# USB_HS_DEVICE.net
KiCad netlist of a schematic drawn in Altium Designer
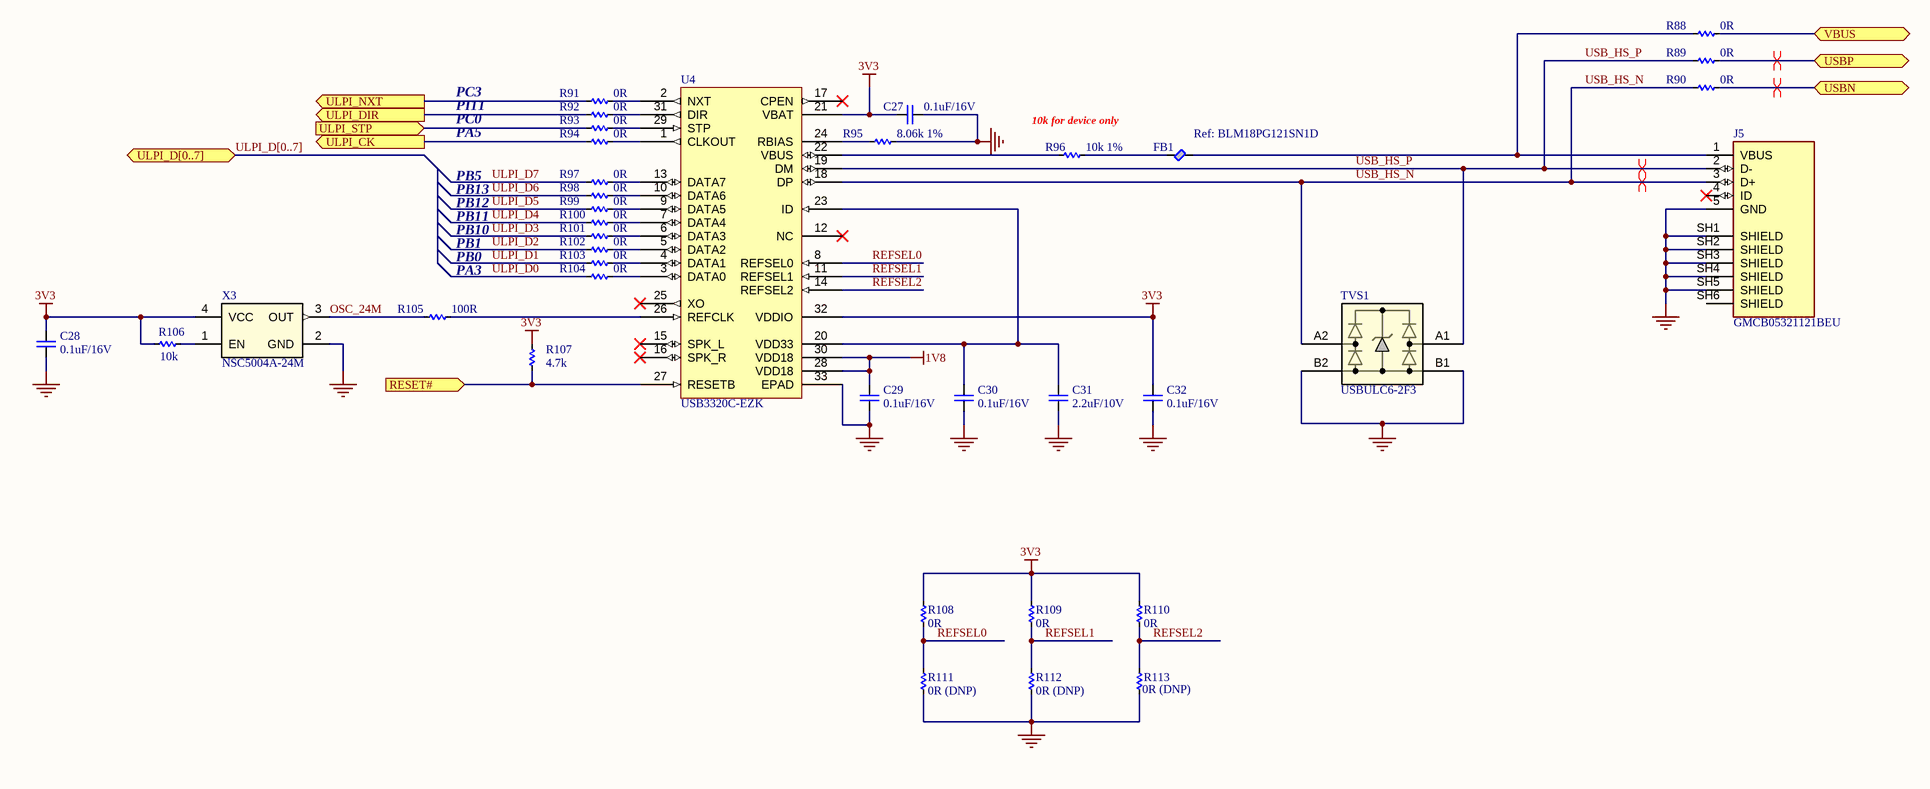
[diagram p0: USB_HS_DEVICE.SchDoc]

(export (version "E")
  (design (tool "Eeschema 10.0.6"))
  (components
    (comp (ref "C27")
      (value "0.1uF/16V")
      (footprint "CAP_C_1608X80")
      (description "CAP_Chip")
      (libsource (lib "LABLIB") (part "CAP_SMD"))
    )
    (comp (ref "C28")
      (value "0.1uF/16V")
      (footprint "CAP_C_1608X80")
      (description "CAP_Chip")
      (libsource (lib "LABLIB") (part "CAP_SMD"))
    )
    (comp (ref "C29")
      (value "0.1uF/16V")
      (footprint "CAP_C_1608X80")
      (description "CAP_Chip")
      (libsource (lib "LABLIB") (part "CAP_SMD"))
    )
    (comp (ref "C30")
      (value "0.1uF/16V")
      (footprint "CAP_C_1608X80")
      (description "CAP_Chip")
      (libsource (lib "LABLIB") (part "CAP_SMD"))
    )
    (comp (ref "C31")
      (value "2.2uF/10V")
      (footprint "CAP_C_1608X80")
      (description "CAP_Chip")
      (libsource (lib "LABLIB") (part "CAP_SMD"))
    )
    (comp (ref "C32")
      (value "0.1uF/16V")
      (footprint "CAP_C_1608X80")
      (description "CAP_Chip")
      (libsource (lib "LABLIB") (part "CAP_SMD"))
    )
    (comp (ref "FB1")
      (value "FB")
      (footprint "IND_1608x65")
      (description "FERRITE BEAD")
      (libsource (lib "COMM_SCHLIB") (part "FB"))
    )
    (comp (ref "J5")
      (value "GMCB05321121BEU")
      (footprint "AMPHENOL_GMCB05321121BEU")
      (description "Micro USB 2.0 Type B Receptacle Right Angle SMT, Tape and Reel Packaging")
      (fields (field (name "MF") "Amphenol Commercial Products"))
      (libsource (lib "COMM_SCHLIB") (part "GMCB05321121BEU"))
    )
    (comp (ref "R88")
      (value "0R")
      (footprint "RES_C_1608X60")
      (description "RES")
      (libsource (lib "LABLIB") (part "_RES_B_2"))
    )
    (comp (ref "R89")
      (value "0R")
      (footprint "RES_C_1608X60")
      (description "RES")
      (libsource (lib "LABLIB") (part "_RES_B_2"))
    )
    (comp (ref "R90")
      (value "0R")
      (footprint "RES_C_1608X60")
      (description "RES")
      (libsource (lib "LABLIB") (part "_RES_B_2"))
    )
    (comp (ref "R91")
      (value "0R")
      (footprint "RES_C_1608X60")
      (description "RES")
      (libsource (lib "LABLIB") (part "_RES_B_2"))
    )
    (comp (ref "R92")
      (value "0R")
      (footprint "RES_C_1608X60")
      (description "RES")
      (libsource (lib "LABLIB") (part "_RES_B_2"))
    )
    (comp (ref "R93")
      (value "0R")
      (footprint "RES_C_1608X60")
      (description "RES")
      (libsource (lib "LABLIB") (part "_RES_B_2"))
    )
    (comp (ref "R94")
      (value "0R")
      (footprint "RES_C_1608X60")
      (description "RES")
      (libsource (lib "LABLIB") (part "_RES_B_2"))
    )
    (comp (ref "R95")
      (value "8.06k 1%")
      (footprint "RES_C_1608X60")
      (description "RES")
      (libsource (lib "LABLIB") (part "_RES_B_2"))
    )
    (comp (ref "R96")
      (value "10k 1%")
      (footprint "RES_C_1608X60")
      (description "RES")
      (libsource (lib "LABLIB") (part "_RES_B_2"))
    )
    (comp (ref "R97")
      (value "0R")
      (footprint "RES_C_1608X60")
      (description "RES")
      (libsource (lib "LABLIB") (part "_RES_B_2"))
    )
    (comp (ref "R98")
      (value "0R")
      (footprint "RES_C_1608X60")
      (description "RES")
      (libsource (lib "LABLIB") (part "_RES_B_2"))
    )
    (comp (ref "R99")
      (value "0R")
      (footprint "RES_C_1608X60")
      (description "RES")
      (libsource (lib "LABLIB") (part "_RES_B_2"))
    )
    (comp (ref "R100")
      (value "0R")
      (footprint "RES_C_1608X60")
      (description "RES")
      (libsource (lib "LABLIB") (part "_RES_B_2"))
    )
    (comp (ref "R101")
      (value "0R")
      (footprint "RES_C_1608X60")
      (description "RES")
      (libsource (lib "LABLIB") (part "_RES_B_2"))
    )
    (comp (ref "R102")
      (value "0R")
      (footprint "RES_C_1608X60")
      (description "RES")
      (libsource (lib "LABLIB") (part "_RES_B_2"))
    )
    (comp (ref "R103")
      (value "0R")
      (footprint "RES_C_1608X60")
      (description "RES")
      (libsource (lib "LABLIB") (part "_RES_B_2"))
    )
    (comp (ref "R104")
      (value "0R")
      (footprint "RES_C_1608X60")
      (description "RES")
      (libsource (lib "LABLIB") (part "_RES_B_2"))
    )
    (comp (ref "R105")
      (value "100R")
      (footprint "RES_C_1608X60")
      (description "RES")
      (libsource (lib "LABLIB") (part "_RES_B_2"))
    )
    (comp (ref "R106")
      (value "10k")
      (footprint "RES_C_1608X60")
      (description "RES")
      (libsource (lib "LABLIB") (part "_RES_B_2"))
    )
    (comp (ref "R107")
      (value "4.7k")
      (footprint "RES_C_1608X60")
      (description "RES")
      (libsource (lib "LABLIB") (part "_RES_B_2"))
    )
    (comp (ref "R108")
      (value "0R")
      (footprint "RES_C_1608X60")
      (description "RES")
      (libsource (lib "LABLIB") (part "_RES_B_2"))
    )
    (comp (ref "R109")
      (value "0R")
      (footprint "RES_C_1608X60")
      (description "RES")
      (libsource (lib "LABLIB") (part "_RES_B_2"))
    )
    (comp (ref "R110")
      (value "0R")
      (footprint "RES_C_1608X60")
      (description "RES")
      (libsource (lib "LABLIB") (part "_RES_B_2"))
    )
    (comp (ref "R111")
      (value "0R (DNP)")
      (footprint "RES_C_1608X60")
      (description "RES")
      (libsource (lib "LABLIB") (part "_RES_B_2"))
    )
    (comp (ref "R112")
      (value "0R (DNP)")
      (footprint "RES_C_1608X60")
      (description "RES")
      (libsource (lib "LABLIB") (part "_RES_B_2"))
    )
    (comp (ref "R113")
      (value "0R (DNP)")
      (footprint "RES_C_1608X60")
      (description "RES")
      (libsource (lib "LABLIB") (part "_RES_B_2"))
    )
    (comp (ref "TVS1")
      (value "USBULC6-2F3")
      (footprint "FLIPCHIP4_USBUL_STM")
      (description "TVS DIODE 3VWM 4FLIPCHIP")
      (fields (field (name "COPYRIGHT") "Copyright (C) 2025 Ultra Librarian. All rights reserved."))
      (libsource (lib "COMM_SCHLIB") (part "USBULC6-2F3"))
    )
    (comp (ref "U4")
      (value "USB3320C-EZK")
      (footprint "QFN32_5X5MC_MCH")
      (description "IC TRANSCEIVER HALF 1/1 32QFN")
      (libsource (lib "COMM_SCHLIB") (part "USB3320C-EZK"))
    )
    (comp (ref "X3")
      (value "NSC5004A-24M")
      (footprint "NSC5004D-25M")
      (description "XTAL OSC XO 24.0000MHZ CMOS SMD")
      (fields
        (field (name "MANUFACTURER_PART_NUMBER") "NSC5004A-25M")
        (field (name "COPYRIGHT") "Copyright (C) 2025 Ultra Librarian. All rights reserved.")
      )
      (libsource (lib "COMM_SCHLIB") (part "NSC5004D-25M"))
    )
  )
  (nets
    (net (code "1") (name "/OSC_24M") (class "Default")
      (node (ref "R105") (pin "2") (pinfunction "2_2") (pintype "passive"))
      (node (ref "X3") (pin "3") (pinfunction "OUT_3") (pintype "output"))
    )
    (net (code "2") (name "/REFSEL0") (class "Default")
      (node (ref "R108") (pin "2") (pinfunction "2_2") (pintype "passive"))
      (node (ref "R111") (pin "1") (pinfunction "1_1") (pintype "passive"))
      (node (ref "U4") (pin "8") (pinfunction "REFSEL0_8") (pintype "input"))
    )
    (net (code "3") (name "/REFSEL1") (class "Default")
      (node (ref "R109") (pin "2") (pinfunction "2_2") (pintype "passive"))
      (node (ref "R112") (pin "1") (pinfunction "1_1") (pintype "passive"))
      (node (ref "U4") (pin "11") (pinfunction "REFSEL1_11") (pintype "input"))
    )
    (net (code "4") (name "/REFSEL2") (class "Default")
      (node (ref "R110") (pin "2") (pinfunction "2_2") (pintype "passive"))
      (node (ref "R113") (pin "1") (pinfunction "1_1") (pintype "passive"))
      (node (ref "U4") (pin "14") (pinfunction "REFSEL2_14") (pintype "input"))
    )
    (net (code "5") (name "/RESET#") (class "Default")
      (node (ref "R107") (pin "2") (pinfunction "2_2") (pintype "passive"))
      (node (ref "U4") (pin "27") (pinfunction "RESETB_27") (pintype "input"))
    )
    (net (code "6") (name "/ULPI_CK") (class "Default")
      (node (ref "R94") (pin "2") (pinfunction "2_2") (pintype "passive"))
    )
    (net (code "7") (name "/ULPI_D0") (class "Default")
      (node (ref "R104") (pin "2") (pinfunction "2_2") (pintype "passive"))
    )
    (net (code "8") (name "/ULPI_D1") (class "Default")
      (node (ref "R103") (pin "2") (pinfunction "2_2") (pintype "passive"))
    )
    (net (code "9") (name "/ULPI_D2") (class "Default")
      (node (ref "R102") (pin "2") (pinfunction "2_2") (pintype "passive"))
    )
    (net (code "10") (name "/ULPI_D3") (class "Default")
      (node (ref "R101") (pin "2") (pinfunction "2_2") (pintype "passive"))
    )
    (net (code "11") (name "/ULPI_D4") (class "Default")
      (node (ref "R100") (pin "2") (pinfunction "2_2") (pintype "passive"))
    )
    (net (code "12") (name "/ULPI_D5") (class "Default")
      (node (ref "R99") (pin "2") (pinfunction "2_2") (pintype "passive"))
    )
    (net (code "13") (name "/ULPI_D6") (class "Default")
      (node (ref "R98") (pin "2") (pinfunction "2_2") (pintype "passive"))
    )
    (net (code "14") (name "/ULPI_D7") (class "Default")
      (node (ref "R97") (pin "2") (pinfunction "2_2") (pintype "passive"))
    )
    (net (code "15") (name "/ULPI_DIR") (class "Default")
      (node (ref "R92") (pin "2") (pinfunction "2_2") (pintype "passive"))
    )
    (net (code "17") (name "/ULPI_NXT") (class "Default")
      (node (ref "R91") (pin "2") (pinfunction "2_2") (pintype "passive"))
    )
    (net (code "18") (name "/ULPI_STP") (class "Default")
      (node (ref "R93") (pin "2") (pinfunction "2_2") (pintype "passive"))
    )
    (net (code "19") (name "/USBN") (class "Default")
      (node (ref "R90") (pin "2") (pinfunction "2_2") (pintype "passive"))
    )
    (net (code "20") (name "/USBP") (class "Default")
      (node (ref "R89") (pin "2") (pinfunction "2_2") (pintype "passive"))
    )
    (net (code "21") (name "/USB_HS_N") (class "Default")
      (node (ref "J5") (pin "3") (pinfunction "D+_3") (pintype "bidirectional"))
      (node (ref "R90") (pin "1") (pinfunction "1_1") (pintype "passive"))
      (node (ref "TVS1") (pin "A2") (pinfunction "A2_A2") (pintype "passive"))
      (node (ref "U4") (pin "18") (pinfunction "DP_18") (pintype "bidirectional"))
    )
    (net (code "22") (name "/USB_HS_P") (class "Default")
      (node (ref "J5") (pin "2") (pinfunction "D-_2") (pintype "bidirectional"))
      (node (ref "R89") (pin "1") (pinfunction "1_1") (pintype "passive"))
      (node (ref "TVS1") (pin "A1") (pinfunction "A1_A1") (pintype "passive"))
      (node (ref "U4") (pin "19") (pinfunction "DM_19") (pintype "bidirectional"))
    )
    (net (code "23") (name "/VBUS") (class "Default")
      (node (ref "R88") (pin "2") (pinfunction "2_2") (pintype "passive"))
    )
    (net (code "24") (name "1V8") (class "Default")
      (node (ref "C29") (pin "2") (pinfunction "2_2") (pintype "passive"))
      (node (ref "U4") (pin "28") (pinfunction "VDD18_28") (pintype "power_in"))
      (node (ref "U4") (pin "30") (pinfunction "VDD18_30") (pintype "power_in"))
    )
    (net (code "25") (name "3V3") (class "Default")
      (node (ref "C27") (pin "2") (pinfunction "2_2") (pintype "passive"))
      (node (ref "C28") (pin "2") (pinfunction "2_2") (pintype "passive"))
      (node (ref "C32") (pin "2") (pinfunction "2_2") (pintype "passive"))
      (node (ref "R106") (pin "2") (pinfunction "2_2") (pintype "passive"))
      (node (ref "R107") (pin "1") (pinfunction "1_1") (pintype "passive"))
      (node (ref "R108") (pin "1") (pinfunction "1_1") (pintype "passive"))
      (node (ref "R109") (pin "1") (pinfunction "1_1") (pintype "passive"))
      (node (ref "R110") (pin "1") (pinfunction "1_1") (pintype "passive"))
      (node (ref "U4") (pin "21") (pinfunction "VBAT_21") (pintype "power_in"))
      (node (ref "U4") (pin "32") (pinfunction "VDDIO_32") (pintype "power_in"))
      (node (ref "X3") (pin "4") (pinfunction "VCC_4") (pintype "power_in"))
    )
    (net (code "26") (name "GND") (class "Default")
      (node (ref "C27") (pin "1") (pinfunction "1_1") (pintype "passive"))
      (node (ref "C28") (pin "1") (pinfunction "1_1") (pintype "passive"))
      (node (ref "C29") (pin "1") (pinfunction "1_1") (pintype "passive"))
      (node (ref "C30") (pin "1") (pinfunction "1_1") (pintype "passive"))
      (node (ref "C31") (pin "1") (pinfunction "1_1") (pintype "passive"))
      (node (ref "C32") (pin "1") (pinfunction "1_1") (pintype "passive"))
      (node (ref "J5") (pin "5") (pinfunction "GND_5") (pintype "power_in"))
      (node (ref "J5") (pin "SH1") (pinfunction "SHIELD_SH1") (pintype "passive"))
      (node (ref "J5") (pin "SH2") (pinfunction "SHIELD_SH2") (pintype "passive"))
      (node (ref "J5") (pin "SH3") (pinfunction "SHIELD_SH3") (pintype "passive"))
      (node (ref "J5") (pin "SH4") (pinfunction "SHIELD_SH4") (pintype "passive"))
      (node (ref "J5") (pin "SH5") (pinfunction "SHIELD_SH5") (pintype "passive"))
      (node (ref "R111") (pin "2") (pinfunction "2_2") (pintype "passive"))
      (node (ref "R112") (pin "2") (pinfunction "2_2") (pintype "passive"))
      (node (ref "R113") (pin "2") (pinfunction "2_2") (pintype "passive"))
      (node (ref "R95") (pin "2") (pinfunction "2_2") (pintype "passive"))
      (node (ref "TVS1") (pin "B1") (pinfunction "B1_B1") (pintype "passive"))
      (node (ref "TVS1") (pin "B2") (pinfunction "B2_B2") (pintype "passive"))
      (node (ref "U4") (pin "33") (pinfunction "EPAD_33") (pintype "passive"))
      (node (ref "X3") (pin "2") (pinfunction "GND_2") (pintype "power_in"))
    )
    (net (code "27") (name "Net-(FB1-Pad1)") (class "Default")
      (node (ref "FB1") (pin "1") (pinfunction "1_1") (pintype "passive"))
      (node (ref "R96") (pin "2") (pinfunction "2_2") (pintype "passive"))
    )
    (net (code "28") (name "Net-(J5-VBUS)") (class "Default")
      (node (ref "FB1") (pin "2") (pinfunction "2_2") (pintype "passive"))
      (node (ref "J5") (pin "1") (pinfunction "VBUS_1") (pintype "power_in"))
      (node (ref "R88") (pin "1") (pinfunction "1_1") (pintype "passive"))
    )
    (net (code "29") (name "Net-(U4-CLKOUT)") (class "Default")
      (node (ref "R94") (pin "1") (pinfunction "1_1") (pintype "passive"))
      (node (ref "U4") (pin "1") (pinfunction "CLKOUT_1") (pintype "output"))
    )
    (net (code "30") (name "Net-(U4-DATA0)") (class "Default")
      (node (ref "R104") (pin "1") (pinfunction "1_1") (pintype "passive"))
      (node (ref "U4") (pin "3") (pinfunction "DATA0_3") (pintype "bidirectional"))
    )
    (net (code "31") (name "Net-(U4-DATA1)") (class "Default")
      (node (ref "R103") (pin "1") (pinfunction "1_1") (pintype "passive"))
      (node (ref "U4") (pin "4") (pinfunction "DATA1_4") (pintype "bidirectional"))
    )
    (net (code "32") (name "Net-(U4-DATA2)") (class "Default")
      (node (ref "R102") (pin "1") (pinfunction "1_1") (pintype "passive"))
      (node (ref "U4") (pin "5") (pinfunction "DATA2_5") (pintype "bidirectional"))
    )
    (net (code "33") (name "Net-(U4-DATA3)") (class "Default")
      (node (ref "R101") (pin "1") (pinfunction "1_1") (pintype "passive"))
      (node (ref "U4") (pin "6") (pinfunction "DATA3_6") (pintype "bidirectional"))
    )
    (net (code "34") (name "Net-(U4-DATA4)") (class "Default")
      (node (ref "R100") (pin "1") (pinfunction "1_1") (pintype "passive"))
      (node (ref "U4") (pin "7") (pinfunction "DATA4_7") (pintype "bidirectional"))
    )
    (net (code "35") (name "Net-(U4-DATA5)") (class "Default")
      (node (ref "R99") (pin "1") (pinfunction "1_1") (pintype "passive"))
      (node (ref "U4") (pin "9") (pinfunction "DATA5_9") (pintype "bidirectional"))
    )
    (net (code "36") (name "Net-(U4-DATA6)") (class "Default")
      (node (ref "R98") (pin "1") (pinfunction "1_1") (pintype "passive"))
      (node (ref "U4") (pin "10") (pinfunction "DATA6_10") (pintype "bidirectional"))
    )
    (net (code "37") (name "Net-(U4-DATA7)") (class "Default")
      (node (ref "R97") (pin "1") (pinfunction "1_1") (pintype "passive"))
      (node (ref "U4") (pin "13") (pinfunction "DATA7_13") (pintype "bidirectional"))
    )
    (net (code "38") (name "Net-(U4-DIR)") (class "Default")
      (node (ref "R92") (pin "1") (pinfunction "1_1") (pintype "passive"))
      (node (ref "U4") (pin "31") (pinfunction "DIR_31") (pintype "output"))
    )
    (net (code "39") (name "Net-(U4-ID)") (class "Default")
      (node (ref "C30") (pin "2") (pinfunction "2_2") (pintype "passive"))
      (node (ref "C31") (pin "2") (pinfunction "2_2") (pintype "passive"))
      (node (ref "U4") (pin "20") (pinfunction "VDD33_20") (pintype "power_in"))
      (node (ref "U4") (pin "23") (pinfunction "ID_23") (pintype "input"))
    )
    (net (code "40") (name "Net-(U4-NXT)") (class "Default")
      (node (ref "R91") (pin "1") (pinfunction "1_1") (pintype "passive"))
      (node (ref "U4") (pin "2") (pinfunction "NXT_2") (pintype "output"))
    )
    (net (code "41") (name "Net-(U4-RBIAS)") (class "Default")
      (node (ref "R95") (pin "1") (pinfunction "1_1") (pintype "passive"))
      (node (ref "U4") (pin "24") (pinfunction "RBIAS_24") (pintype "passive"))
    )
    (net (code "42") (name "Net-(U4-REFCLK)") (class "Default")
      (node (ref "R105") (pin "1") (pinfunction "1_1") (pintype "passive"))
      (node (ref "U4") (pin "26") (pinfunction "REFCLK_26") (pintype "input"))
    )
    (net (code "43") (name "Net-(U4-STP)") (class "Default")
      (node (ref "R93") (pin "1") (pinfunction "1_1") (pintype "passive"))
      (node (ref "U4") (pin "29") (pinfunction "STP_29") (pintype "input"))
    )
    (net (code "44") (name "Net-(U4-VBUS)") (class "Default")
      (node (ref "R96") (pin "1") (pinfunction "1_1") (pintype "passive"))
      (node (ref "U4") (pin "22") (pinfunction "VBUS_22") (pintype "bidirectional"))
    )
    (net (code "45") (name "Net-(X3-EN)") (class "Default")
      (node (ref "R106") (pin "1") (pinfunction "1_1") (pintype "passive"))
      (node (ref "X3") (pin "1") (pinfunction "EN_1") (pintype "passive"))
    )
    (net (code "46") (name "unconnected-(J5-ID-Pad4)") (class "Default")
      (node (ref "J5") (pin "4") (pinfunction "ID_4") (pintype "bidirectional+no_connect"))
    )
    (net (code "47") (name "unconnected-(J5-SHIELD-PadSH6)") (class "Default")
      (node (ref "J5") (pin "SH6") (pinfunction "SHIELD_SH6") (pintype "passive"))
    )
    (net (code "48") (name "unconnected-(U4-CPEN-Pad17)") (class "Default")
      (node (ref "U4") (pin "17") (pinfunction "CPEN_17") (pintype "output+no_connect"))
    )
    (net (code "49") (name "unconnected-(U4-NC-Pad12)") (class "Default")
      (node (ref "U4") (pin "12") (pinfunction "NC_12") (pintype "passive+no_connect"))
    )
    (net (code "50") (name "unconnected-(U4-SPK_L-Pad15)") (class "Default")
      (node (ref "U4") (pin "15") (pinfunction "SPK_L_15") (pintype "bidirectional+no_connect"))
    )
    (net (code "51") (name "unconnected-(U4-SPK_R-Pad16)") (class "Default")
      (node (ref "U4") (pin "16") (pinfunction "SPK_R_16") (pintype "bidirectional+no_connect"))
    )
    (net (code "52") (name "unconnected-(U4-XO-Pad25)") (class "Default")
      (node (ref "U4") (pin "25") (pinfunction "XO_25") (pintype "output+no_connect"))
    )
  )
)
